# waffling80-NMB-USB.net
KiCad netlist of a schematic drawn in Altium Designer
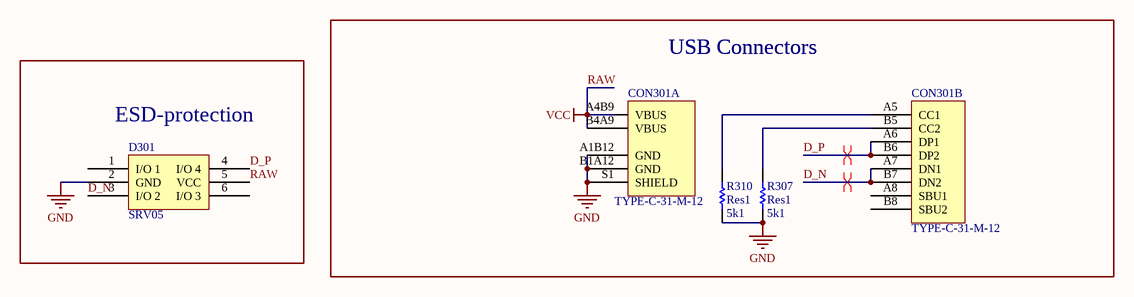
[diagram p0: waffling80-NMB-USB.SchDoc]

(export (version "E")
  (design (tool "Eeschema 10.0.6"))
  (components
    (comp (ref "CON301")
      (value "TYPE-C-31-M-12")
      (footprint "TYPE-C-31-M-12")
      (fields (field (name "MFG") "Korean Hroparts Elec") (field (name "LCSC PART #") "C165948"))
      (libsource (lib "Schlib1") (part "TYPE-C-31-M-12"))
    )
    (comp (ref "D301")
      (value "SRV05")
      (footprint "SOT-23-6")
      (fields (field (name "LCSC PART #") "C85364") (field (name "MRF.PART") "SRV05-4-P-T7"))
      (libsource (lib "Keebs") (part "SRV05"))
    )
    (comp (ref "R307")
      (value "Res1")
      (footprint "R0603[1608]")
      (description "Resistor")
      (fields
        (field (name "ALTIUM_VALUE") "5k1")
        (field (name "MFG") "Panasonic Electronic Components")
        (field (name "LCSC PART #") "C23186")
      )
      (libsource (lib "Miscellaneous Devices") (part "Res1"))
    )
    (comp (ref "R310")
      (value "Res1")
      (footprint "R0603[1608]")
      (description "Resistor")
      (fields
        (field (name "ALTIUM_VALUE") "5k1")
        (field (name "MFG") "Panasonic Electronic Components")
        (field (name "LCSC PART #") "C23186")
      )
      (libsource (lib "Miscellaneous Devices") (part "Res1"))
    )
  )
  (nets
    (net (code "1") (name "/D_N") (class "Default")
      (node (ref "CON301") (pin "A7") (pinfunction "DN1_A7") (pintype "passive"))
      (node (ref "CON301") (pin "B7") (pinfunction "DN2_B7") (pintype "passive"))
      (node (ref "D301") (pin "3") (pinfunction "I/O_2_3") (pintype "passive"))
    )
    (net (code "2") (name "/D_P") (class "Default")
      (node (ref "CON301") (pin "A6") (pinfunction "DP1_A6") (pintype "passive"))
      (node (ref "CON301") (pin "B6") (pinfunction "DP2_B6") (pintype "passive"))
      (node (ref "D301") (pin "4") (pinfunction "I/O_4_4") (pintype "passive"))
    )
    (net (code "3") (name "GND") (class "Default")
      (node (ref "CON301") (pin "A1B12") (pinfunction "GND_A1B12") (pintype "passive"))
      (node (ref "CON301") (pin "B1A12") (pinfunction "GND_B1A12") (pintype "passive"))
      (node (ref "CON301") (pin "S1") (pinfunction "SHIELD_S1") (pintype "passive"))
      (node (ref "D301") (pin "2") (pinfunction "GND_2") (pintype "passive"))
      (node (ref "R307") (pin "2") (pinfunction "2_2") (pintype "passive"))
      (node (ref "R310") (pin "2") (pinfunction "2_2") (pintype "passive"))
    )
    (net (code "4") (name "Net-(CON301B-CC1)") (class "Default")
      (node (ref "CON301") (pin "A5") (pinfunction "CC1_A5") (pintype "passive"))
      (node (ref "R310") (pin "1") (pinfunction "1_1") (pintype "passive"))
    )
    (net (code "5") (name "Net-(CON301B-CC2)") (class "Default")
      (node (ref "CON301") (pin "B5") (pinfunction "CC2_B5") (pintype "passive"))
      (node (ref "R307") (pin "1") (pinfunction "1_1") (pintype "passive"))
    )
    (net (code "6") (name "VCC") (class "Default")
      (node (ref "CON301") (pin "A4B9") (pinfunction "VBUS_A4B9") (pintype "passive"))
      (node (ref "CON301") (pin "B4A9") (pinfunction "VBUS_B4A9") (pintype "passive"))
      (node (ref "D301") (pin "5") (pinfunction "VCC_5") (pintype "passive"))
    )
    (net (code "7") (name "unconnected-(CON301B-SBU1-PadA8)") (class "Default")
      (node (ref "CON301") (pin "A8") (pinfunction "SBU1_A8") (pintype "passive"))
    )
    (net (code "8") (name "unconnected-(CON301B-SBU2-PadB8)") (class "Default")
      (node (ref "CON301") (pin "B8") (pinfunction "SBU2_B8") (pintype "passive"))
    )
    (net (code "9") (name "unconnected-(D301-I{slash}O_1-Pad1)") (class "Default")
      (node (ref "D301") (pin "1") (pinfunction "I/O_1_1") (pintype "passive"))
    )
    (net (code "10") (name "unconnected-(D301-I{slash}O_3-Pad6)") (class "Default")
      (node (ref "D301") (pin "6") (pinfunction "I/O_3_6") (pintype "passive"))
    )
  )
)
